# MainControl_A3.net
KiCad netlist of a schematic drawn in Altium Designer
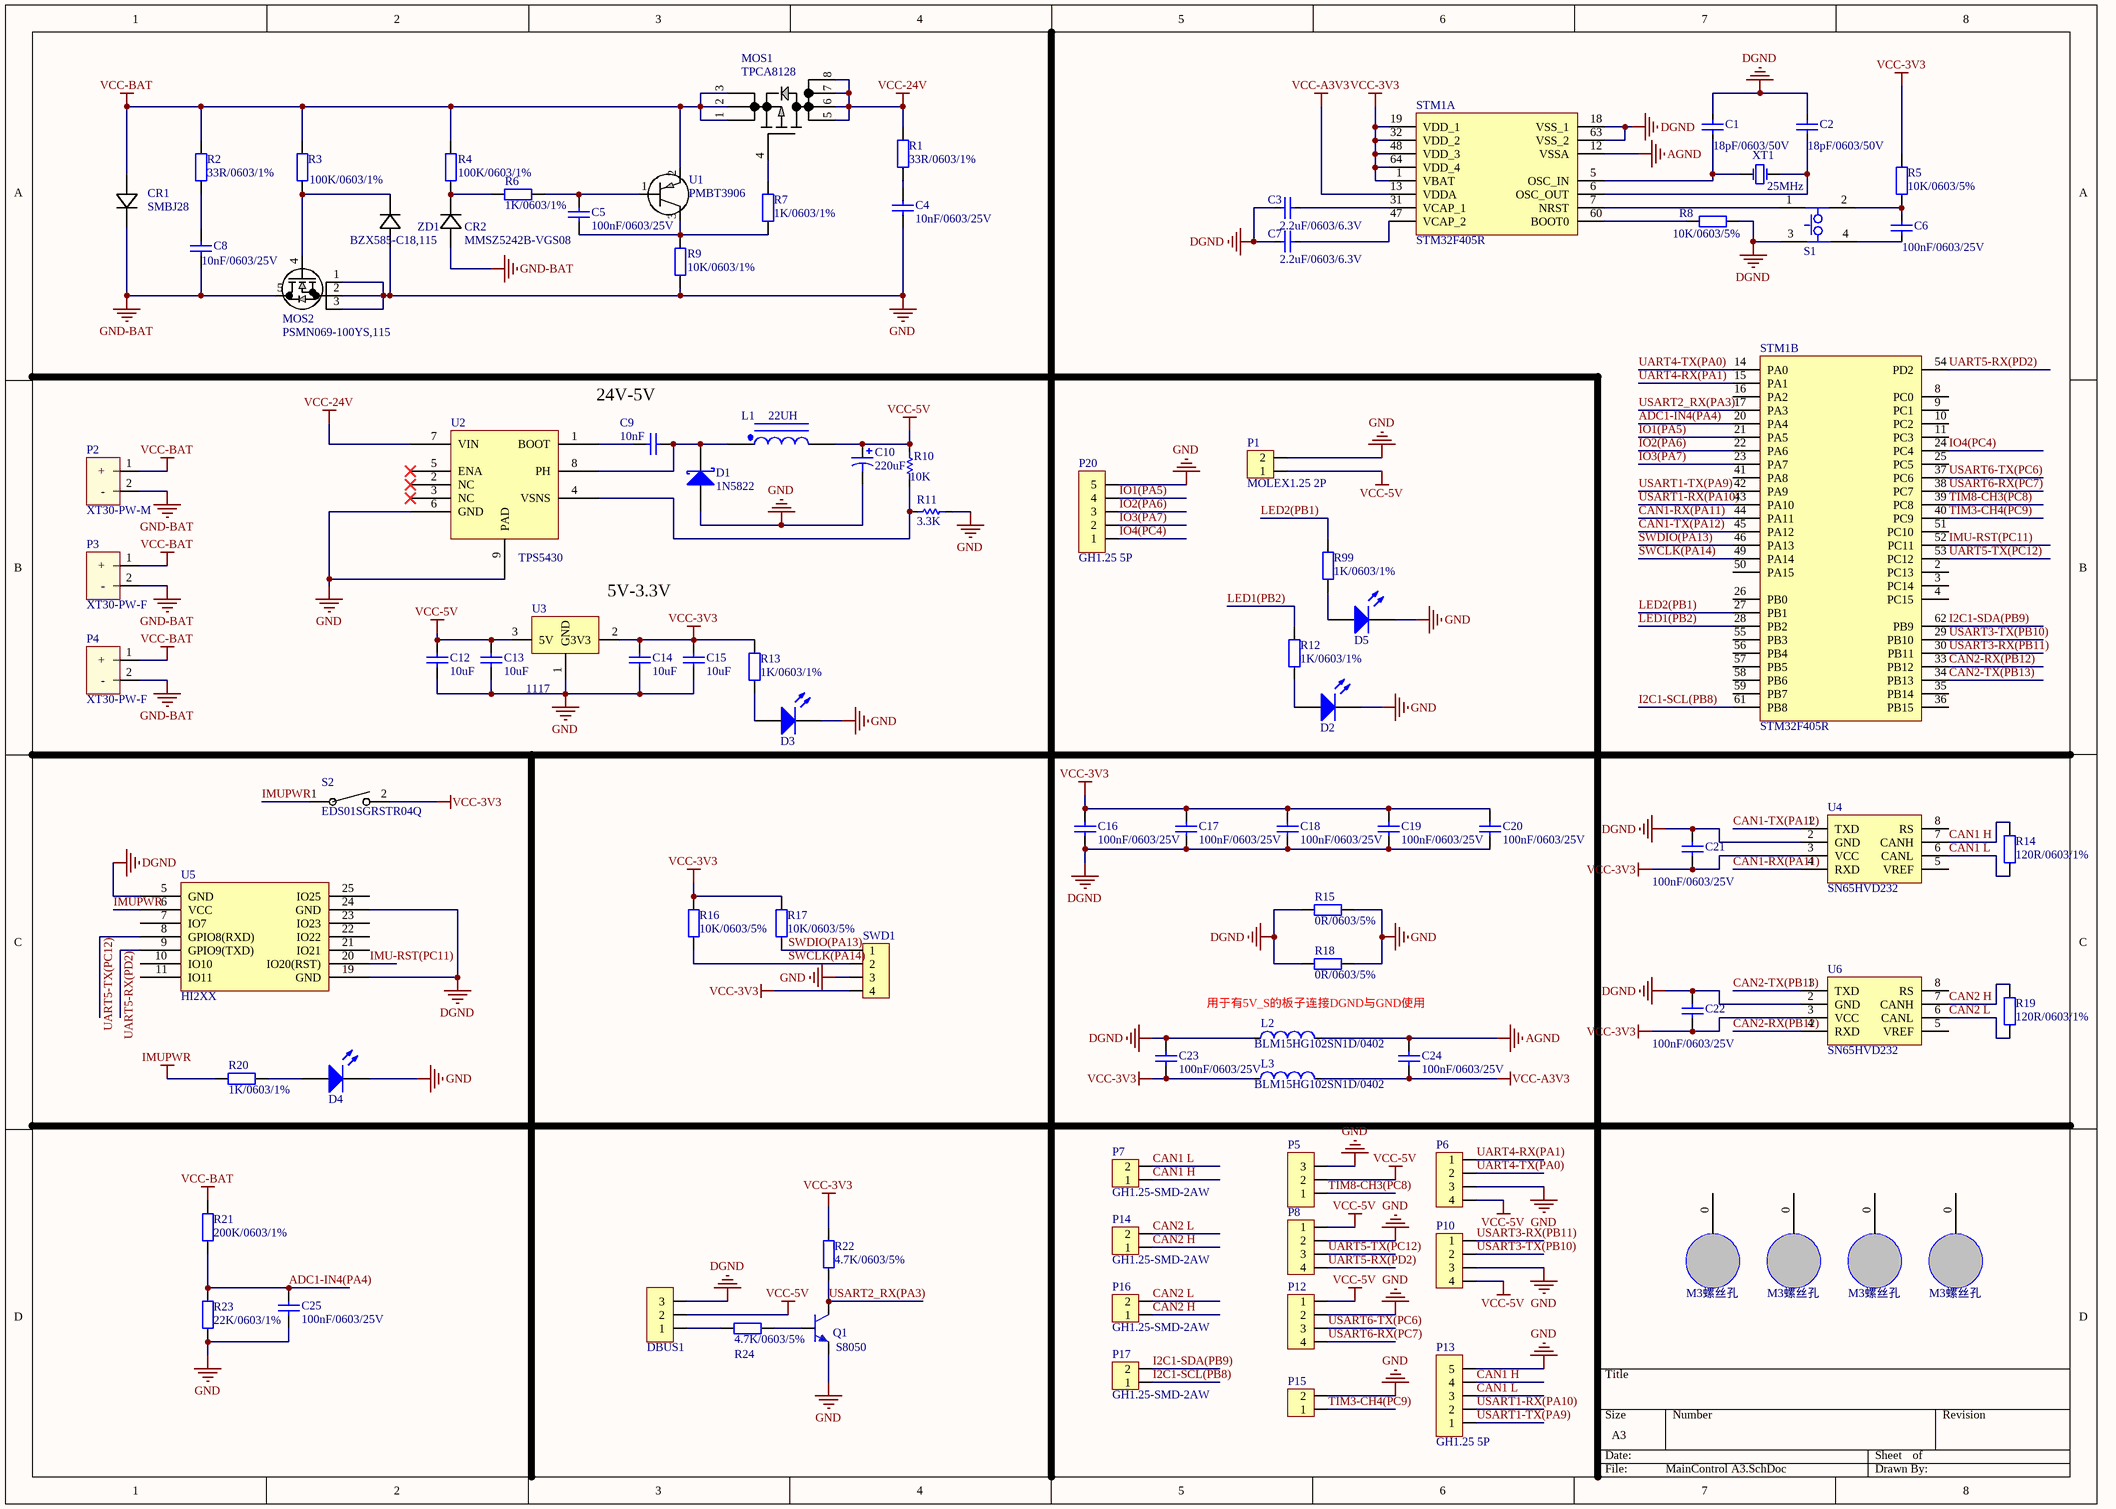
[diagram p0: MainControl A3.SchDoc]

(export (version "E")
  (design (tool "Eeschema 10.0.6"))
  (components
    (comp (ref "C1")
      (value "18pF/0603/50V")
      (footprint "C-SMD-0603")
      (description "Capacitor")
      (fields (field (name "Comment") "18pF"))
      (libsource (lib "SCH_Passive") (part "Cap_0402"))
    )
    (comp (ref "C2")
      (value "18pF/0603/50V")
      (footprint "C-SMD-0603")
      (description "Capacitor")
      (fields (field (name "Comment") "18pF"))
      (libsource (lib "SCH_Passive") (part "Cap_0402"))
    )
    (comp (ref "C3")
      (value "2.2uF/0603/6.3V")
      (footprint "C-SMD-0603")
      (description "Capacitor")
      (fields (field (name "Comment") "2.2uF"))
      (libsource (lib "SCH_Passive") (part "Cap_0402"))
    )
    (comp (ref "C4")
      (value "10nF/0603/25V")
      (footprint "C-SMD-0603")
      (description "贴片电容")
      (fields (field (name "Comment") "10nF") (field (name "PUBLISHER") "Altium Limited"))
      (libsource (lib "三代主控板原理图库") (part "Cap"))
    )
    (comp (ref "C5")
      (value "100nF/0603/25V")
      (footprint "C-SMD-0603")
      (description "贴片电容")
      (fields (field (name "Comment") "100nF") (field (name "PUBLISHER") "Altium Limited"))
      (libsource (lib "三代主控板原理图库") (part "Cap"))
    )
    (comp (ref "C6")
      (value "100nF/0603/25V")
      (footprint "C-SMD-0603")
      (description "Capacitor")
      (fields (field (name "Comment") "100nF"))
      (libsource (lib "SCH_Passive") (part "Cap_0402"))
    )
    (comp (ref "C7")
      (value "2.2uF/0603/6.3V")
      (footprint "C-SMD-0603")
      (description "Capacitor")
      (fields (field (name "Comment") "2.2uF"))
      (libsource (lib "SCH_Passive") (part "Cap_0402"))
    )
    (comp (ref "C8")
      (value "10nF/0603/25V")
      (footprint "C-SMD-0603")
      (description "贴片电容")
      (fields (field (name "Comment") "10nF") (field (name "PUBLISHER") "Altium Limited"))
      (libsource (lib "三代主控板原理图库") (part "Cap"))
    )
    (comp (ref "C9")
      (value "10nF")
      (footprint "C-SMD-0603")
      (description "无极性电容")
      (fields (field (name "PUBLISHER") "Altium Limited"))
      (libsource (lib "Devices") (part "Cap"))
    )
    (comp (ref "C10")
      (value "220uF")
      (footprint "TCAP7343")
      (description "Polarized Capacitor (Radial)")
      (fields (field (name "PUBLISHER") "Altium Limited"))
      (libsource (lib "Miscellaneous Devices") (part "Cap Pol1"))
    )
    (comp (ref "C12")
      (value "10uF")
      (footprint "C-SMD-0603")
      (description "无极性电容")
      (fields (field (name "PUBLISHER") "Altium Limited"))
      (libsource (lib "Devices") (part "Cap"))
    )
    (comp (ref "C13")
      (value "10uF")
      (footprint "C-SMD-0603")
      (description "无极性电容")
      (fields (field (name "PUBLISHER") "Altium Limited"))
      (libsource (lib "Devices") (part "Cap"))
    )
    (comp (ref "C14")
      (value "10uF")
      (footprint "C-SMD-0603")
      (description "无极性电容")
      (fields (field (name "PUBLISHER") "Altium Limited"))
      (libsource (lib "Devices") (part "Cap"))
    )
    (comp (ref "C15")
      (value "10uF")
      (footprint "C-SMD-0603")
      (description "无极性电容")
      (fields (field (name "PUBLISHER") "Altium Limited"))
      (libsource (lib "Devices") (part "Cap"))
    )
    (comp (ref "C16")
      (value "100nF/0603/25V")
      (footprint "C-SMD-0603")
      (description "贴片电容")
      (fields (field (name "Comment") "100nF") (field (name "PUBLISHER") "Altium Limited"))
      (libsource (lib "三代主控板原理图库") (part "Cap"))
    )
    (comp (ref "C17")
      (value "100nF/0603/25V")
      (footprint "C-SMD-0603")
      (description "贴片电容")
      (fields (field (name "Comment") "100nF") (field (name "PUBLISHER") "Altium Limited"))
      (libsource (lib "三代主控板原理图库") (part "Cap"))
    )
    (comp (ref "C18")
      (value "100nF/0603/25V")
      (footprint "C-SMD-0603")
      (description "贴片电容")
      (fields (field (name "Comment") "100nF") (field (name "PUBLISHER") "Altium Limited"))
      (libsource (lib "三代主控板原理图库") (part "Cap"))
    )
    (comp (ref "C19")
      (value "100nF/0603/25V")
      (footprint "C-SMD-0603")
      (description "贴片电容")
      (fields (field (name "Comment") "100nF") (field (name "PUBLISHER") "Altium Limited"))
      (libsource (lib "三代主控板原理图库") (part "Cap"))
    )
    (comp (ref "C20")
      (value "100nF/0603/25V")
      (footprint "C-SMD-0603")
      (description "贴片电容")
      (fields (field (name "Comment") "100nF") (field (name "PUBLISHER") "Altium Limited"))
      (libsource (lib "三代主控板原理图库") (part "Cap"))
    )
    (comp (ref "C21")
      (value "100nF/0603/25V")
      (footprint "C-SMD-0603")
      (description "贴片电容")
      (fields (field (name "Comment") "100NF") (field (name "PUBLISHER") "Altium Limited"))
      (libsource (lib "三代主控板原理图库") (part "Cap"))
    )
    (comp (ref "C22")
      (value "100nF/0603/25V")
      (footprint "C-SMD-0603")
      (description "贴片电容")
      (fields (field (name "Comment") "100NF") (field (name "PUBLISHER") "Altium Limited"))
      (libsource (lib "三代主控板原理图库") (part "Cap"))
    )
    (comp (ref "C23")
      (value "100nF/0603/25V")
      (footprint "C-SMD-0603")
      (description "贴片电容")
      (fields (field (name "Comment") "100nF") (field (name "PUBLISHER") "Altium Limited"))
      (libsource (lib "三代主控板原理图库") (part "Cap"))
    )
    (comp (ref "C24")
      (value "100nF/0603/25V")
      (footprint "C-SMD-0603")
      (description "贴片电容")
      (fields (field (name "Comment") "100nF") (field (name "PUBLISHER") "Altium Limited"))
      (libsource (lib "三代主控板原理图库") (part "Cap"))
    )
    (comp (ref "C25")
      (value "100nF/0603/25V")
      (footprint "C-SMD-0603")
      (description "贴片电容")
      (fields (field (name "Comment") "100nF") (field (name "PUBLISHER") "Altium Limited"))
      (libsource (lib "三代主控板原理图库") (part "Cap"))
    )
    (comp (ref "CR1")
      (value "SMBJ28")
      (footprint "SMBJSeries_LTF")
      (description "No Description Available")
      (fields
        (field (name "MANUFACTURER_PART_NUMBER") "SMBJ10")
        (field (name "COPYRIGHT") "Copyright (C) 2018 Accelerated Designs. All rights reserved")
      )
      (libsource (lib "SMBJ") (part "SMBJ10"))
    )
    (comp (ref "CR2")
      (value "MMSZ5242B-VGS08")
      (footprint "SOD123_MMS")
      (description "No Description Available")
      (fields (field (name "COPYRIGHT") "Copyright (C) 2018 Accelerated Designs. All rights reserved"))
      (libsource (lib "mmsz") (part "MMSZ5242B-VGS08"))
    )
    (comp (ref "D1")
      (value "1N5822")
      (footprint "SS34")
      (description "Schottky Diode")
      (fields (field (name "PUBLISHER") "Altium Limited"))
      (libsource (lib "Miscellaneous Devices") (part "D Schottky"))
    )
    (comp (ref "D2")
      (value "LED0")
      (footprint "LED-0603")
      (description "发光二极管")
      (fields (field (name "PUBLISHER") "Altium Limited"))
      (libsource (lib "Devices") (part "LED0"))
    )
    (comp (ref "D3")
      (value "LED0")
      (footprint "LED-0603")
      (description "发光二极管")
      (fields (field (name "PUBLISHER") "Altium Limited"))
      (libsource (lib "Devices") (part "LED0"))
    )
    (comp (ref "D4")
      (value "LED0")
      (footprint "LED-0603")
      (description "发光二极管")
      (fields (field (name "PUBLISHER") "Altium Limited"))
      (libsource (lib "Devices") (part "LED0"))
    )
    (comp (ref "D5")
      (value "LED0")
      (footprint "LED-0603")
      (description "发光二极管")
      (fields (field (name "PUBLISHER") "Altium Limited"))
      (libsource (lib "Devices") (part "LED0"))
    )
    (comp (ref "DBUS1")
      (value "Header 3")
      (footprint "HDR1x3")
      (description "Header")
      (fields (field (name "PUBLISHER") "Altium Limited"))
      (libsource (lib "排针排母") (part "Header 3"))
    )
    (comp (ref "L1")
      (value "22UH")
      (footprint "L-7070")
      (description "Magnetic-Core Inductor with Winding Polarity Marking")
      (fields (field (name "PUBLISHER") "Altium Limited"))
      (libsource (lib "Miscellaneous Devices") (part "Inductor Iron Dot"))
    )
    (comp (ref "L2")
      (value "BLM15HG102SN1D/0402")
      (footprint "l-SMD-0402")
      (description "Inductor")
      (fields (field (name "Comment") "BLM15HG102SN1D"))
      (libsource (lib "三代主控板原理图库") (part "BLM15HG102SN1D/0402"))
    )
    (comp (ref "L3")
      (value "BLM15HG102SN1D/0402")
      (footprint "l-SMD-0402")
      (description "Inductor")
      (fields (field (name "Comment") "BLM15HG102SN1D"))
      (libsource (lib "三代主控板原理图库") (part "BLM15HG102SN1D/0402"))
    )
    (comp (ref "M1") (value "M3螺丝孔") (footprint "M3螺丝") (libsource (lib "My_SCHLib") (part "M3螺丝孔")))
    (comp (ref "M2") (value "M3螺丝孔") (footprint "M3螺丝") (libsource (lib "My_SCHLib") (part "M3螺丝孔")))
    (comp (ref "M3") (value "M3螺丝孔") (footprint "M3螺丝") (libsource (lib "My_SCHLib") (part "M3螺丝孔")))
    (comp (ref "M4") (value "M3螺丝孔") (footprint "M3螺丝") (libsource (lib "My_SCHLib") (part "M3螺丝孔")))
    (comp (ref "MOS1")
      (value "TPCA8128")
      (footprint "SOP Advance_TOS")
      (description "No Description Available")
      (fields (field (name "COPYRIGHT") "Copyright (C) 2018 Accelerated Designs. All rights reserved"))
      (libsource (lib "TPCA8122") (part "TPCA8128"))
    )
    (comp (ref "MOS2")
      (value "PSMN069-100YS,115")
      (footprint "LFPAK56_POWER-SO8_SOT669_NEX")
      (description "No Description Available")
      (fields (field (name "COPYRIGHT") "Copyright (C) 2018 Accelerated Designs. All rights reserved"))
      (libsource (lib "psmn") (part "PSMN069-100YS,115"))
    )
    (comp (ref "P1")
      (value "MOLEX1.25 2P")
      (footprint "MOLEX1.25-2P")
      (description "pitch 1.25mm，2P，公座（A代表公，Y代表母），卧贴")
      (libsource (lib "SCH_Connector") (part "GH1.25-SMD-2AW"))
    )
    (comp (ref "P2")
      (value "XT30-PW-M")
      (footprint "XT30PW-M")
      (description "2P电源连接器母座")
      (libsource (lib "机器人队F405新主控1") (part "XT30-F"))
    )
    (comp (ref "P3")
      (value "XT30-PW-F")
      (footprint "XT30PW-F")
      (description "2P电源连接器母座")
      (libsource (lib "机器人队F405新主控1") (part "XT30-F"))
    )
    (comp (ref "P4")
      (value "XT30-PW-F")
      (footprint "XT30PW-F")
      (description "2P电源连接器母座")
      (libsource (lib "机器人队F405新主控1") (part "XT30-F"))
    )
    (comp (ref "P5")
      (value "Header 3")
      (footprint "HDR1X3")
      (description "Header")
      (fields (field (name "PUBLISHER") "Altium Limited"))
      (libsource (lib "排针排母") (part "Header 3"))
    )
    (comp (ref "P6")
      (value "GH1.25-SMD-4AW")
      (footprint "GH1.25-SMD-4AW")
      (description "pitch 1.25mm，4P，公座（A代表公，Y代表母），卧贴")
      (libsource (lib "") (part "GH1.25-SMD-4AW_1"))
    )
    (comp (ref "P7")
      (value "GH1.25-SMD-2AW")
      (footprint "GH1.25-SMD-2AW")
      (description "pitch 1.25mm，2P，公座（A代表公，Y代表母），卧贴")
      (libsource (lib "SCH_Connector") (part "GH1.25-SMD-2AW"))
    )
    (comp (ref "P8")
      (value "GH1.25-SMD-4AW")
      (footprint "GH1.25-SMD-4AW")
      (description "pitch 1.25mm，4P，公座（A代表公，Y代表母），卧贴")
      (libsource (lib "") (part "GH1.25-SMD-4AW_1"))
    )
    (comp (ref "P10")
      (value "GH1.25-SMD-4AW")
      (footprint "GH1.25-SMD-4AW")
      (description "pitch 1.25mm，4P，公座（A代表公，Y代表母），卧贴")
      (libsource (lib "") (part "GH1.25-SMD-4AW_1"))
    )
    (comp (ref "P12")
      (value "GH1.25-SMD-4AW")
      (footprint "GH1.25-SMD-4AW")
      (description "pitch 1.25mm，4P，公座（A代表公，Y代表母），卧贴")
      (libsource (lib "") (part "GH1.25-SMD-4AW_1"))
    )
    (comp (ref "P13")
      (value "GH1.25 5P")
      (footprint "GH1.25-SMD-5AW")
      (libsource (lib "gh1.25 5p") (part "GH1.25 5P"))
    )
    (comp (ref "P14")
      (value "GH1.25-SMD-2AW")
      (footprint "GH1.25-SMD-2AW")
      (description "pitch 1.25mm，2P，公座（A代表公，Y代表母），卧贴")
      (libsource (lib "SCH_Connector") (part "GH1.25-SMD-2AW"))
    )
    (comp (ref "P15")
      (value "GH1.25-SMD-2AW")
      (footprint "GH1.25-SMD-2AW")
      (description "pitch 1.25mm，2P，公座（A代表公，Y代表母），卧贴")
      (libsource (lib "SCH_Connector") (part "GH1.25-SMD-2AW"))
    )
    (comp (ref "P16")
      (value "GH1.25-SMD-2AW")
      (footprint "GH1.25-SMD-2AW")
      (description "pitch 1.25mm，2P，公座（A代表公，Y代表母），卧贴")
      (libsource (lib "SCH_Connector") (part "GH1.25-SMD-2AW"))
    )
    (comp (ref "P17")
      (value "GH1.25-SMD-2AW")
      (footprint "GH1.25-SMD-2AW")
      (description "pitch 1.25mm，2P，公座（A代表公，Y代表母），卧贴")
      (libsource (lib "SCH_Connector") (part "GH1.25-SMD-2AW"))
    )
    (comp (ref "P20")
      (value "GH1.25 5P")
      (footprint "GH1.25-SMD-5AW")
      (libsource (lib "gh1.25 5p") (part "GH1.25 5P"))
    )
    (comp (ref "Q1")
      (value "S8050")
      (footprint "SOT23-3")
      (description "Transistor")
      (libsource (lib "SCH_Active") (part "BJT_NPN"))
    )
    (comp (ref "R1")
      (value "33R/0603/1%")
      (footprint "R-SMD-0603")
      (description "贴片电阻")
      (fields (field (name "Comment") "33R") (field (name "PUBLISHER") "Altium Limited"))
      (libsource (lib "") (part "Res1_1"))
    )
    (comp (ref "R2")
      (value "33R/0603/1%")
      (footprint "R-SMD-0603")
      (description "贴片电阻")
      (fields (field (name "Comment") "33R") (field (name "PUBLISHER") "Altium Limited"))
      (libsource (lib "") (part "Res1_1"))
    )
    (comp (ref "R3")
      (value "100K/0603/1%")
      (footprint "R-SMD-0603")
      (description "贴片电阻")
      (fields (field (name "Comment") "100K") (field (name "PUBLISHER") "Altium Limited"))
      (libsource (lib "") (part "Res1_1"))
    )
    (comp (ref "R4")
      (value "100K/0603/1%")
      (footprint "R-SMD-0603")
      (description "贴片电阻")
      (fields (field (name "Comment") "100K") (field (name "PUBLISHER") "Altium Limited"))
      (libsource (lib "") (part "Res1_1"))
    )
    (comp (ref "R5")
      (value "10K/0603/5%")
      (footprint "R-SMD-0603")
      (description "Resistor")
      (fields (field (name "Comment") "10K"))
      (libsource (lib "") (part "Res_0402_2"))
    )
    (comp (ref "R6")
      (value "1K/0603/1%")
      (footprint "R-SMD-0603")
      (description "贴片电阻")
      (fields (field (name "Comment") "1K") (field (name "PUBLISHER") "Altium Limited"))
      (libsource (lib "") (part "Res1_2"))
    )
    (comp (ref "R7")
      (value "1K/0603/1%")
      (footprint "R-SMD-0603")
      (description "贴片电阻")
      (fields (field (name "Comment") "1K") (field (name "PUBLISHER") "Altium Limited"))
      (libsource (lib "底盘主控") (part "Res1"))
    )
    (comp (ref "R8")
      (value "10K/0603/5%")
      (footprint "R-SMD-0603")
      (description "Resistor")
      (fields (field (name "Comment") "10K"))
      (libsource (lib "SCH_Passive") (part "Res_0402"))
    )
    (comp (ref "R9")
      (value "10K/0603/1%")
      (footprint "R-SMD-0603")
      (description "贴片电阻")
      (fields (field (name "Comment") "10K") (field (name "PUBLISHER") "Altium Limited"))
      (libsource (lib "") (part "Res1_1"))
    )
    (comp (ref "R10")
      (value "10K")
      (footprint "R-SMD-0603")
      (description "贴片电阻")
      (fields (field (name "PUBLISHER") "Altium Limited"))
      (libsource (lib "Devices") (part "Res1"))
    )
    (comp (ref "R11")
      (value "3.3K")
      (footprint "R-SMD-0603")
      (description "贴片电阻")
      (fields (field (name "PUBLISHER") "Altium Limited"))
      (libsource (lib "Devices") (part "Res1"))
    )
    (comp (ref "R12")
      (value "1K/0603/1%")
      (footprint "R-SMD-0603")
      (description "贴片电阻")
      (fields (field (name "Comment") "1K") (field (name "PUBLISHER") "Altium Limited"))
      (libsource (lib "") (part "Res1_1"))
    )
    (comp (ref "R13")
      (value "1K/0603/1%")
      (footprint "R-SMD-0603")
      (description "贴片电阻")
      (fields (field (name "Comment") "1K") (field (name "PUBLISHER") "Altium Limited"))
      (libsource (lib "") (part "Res1_1"))
    )
    (comp (ref "R14")
      (value "120R/0603/1%")
      (footprint "R-SMD-0603")
      (description "贴片电阻")
      (fields (field (name "Comment") "120R"))
      (libsource (lib "三代主控板原理图库") (part "Res"))
    )
    (comp (ref "R15")
      (value "0R/0603/5%")
      (footprint "R-SMD-0603")
      (description "Resistor")
      (fields (field (name "Comment") "0R"))
      (libsource (lib "电容电阻电感") (part "Res_0603"))
    )
    (comp (ref "R16")
      (value "10K/0603/5%")
      (footprint "R-SMD-0603")
      (description "Resistor")
      (fields (field (name "Comment") "10K"))
      (libsource (lib "") (part "Res_0402_1"))
    )
    (comp (ref "R17")
      (value "10K/0603/5%")
      (footprint "R-SMD-0603")
      (description "Resistor")
      (fields (field (name "Comment") "10K"))
      (libsource (lib "") (part "Res_0402_1"))
    )
    (comp (ref "R18")
      (value "0R/0603/5%")
      (footprint "R-SMD-0603")
      (description "Resistor")
      (fields (field (name "Comment") "0R"))
      (libsource (lib "电容电阻电感") (part "Res_0603"))
    )
    (comp (ref "R19")
      (value "120R/0603/1%")
      (footprint "R-SMD-0603")
      (description "贴片电阻")
      (fields (field (name "Comment") "120R"))
      (libsource (lib "三代主控板原理图库") (part "Res"))
    )
    (comp (ref "R20")
      (value "1K/0603/1%")
      (footprint "R-SMD-0603")
      (description "贴片电阻")
      (fields (field (name "Comment") "1K") (field (name "PUBLISHER") "Altium Limited"))
      (libsource (lib "") (part "Res1_2"))
    )
    (comp (ref "R21")
      (value "200K/0603/1%")
      (footprint "R-SMD-0603")
      (description "贴片电阻")
      (fields (field (name "Comment") "200K") (field (name "PUBLISHER") "Altium Limited"))
      (libsource (lib "底盘主控") (part "Res1"))
    )
    (comp (ref "R22")
      (value "4.7K/0603/5%")
      (footprint "R-SMD-0603")
      (description "Resistor")
      (fields (field (name "Comment") "4.7K"))
      (libsource (lib "") (part "Res_0603_1"))
    )
    (comp (ref "R23")
      (value "22K/0603/1%")
      (footprint "R-SMD-0603")
      (description "贴片电阻")
      (fields (field (name "Comment") "22K") (field (name "PUBLISHER") "Altium Limited"))
      (libsource (lib "底盘主控") (part "Res1"))
    )
    (comp (ref "R24")
      (value "4.7K/0603/5%")
      (footprint "R-SMD-0603")
      (description "Resistor")
      (fields (field (name "Comment") "4.7K"))
      (libsource (lib "SCH_Passive") (part "Res_0603"))
    )
    (comp (ref "R99")
      (value "1K/0603/1%")
      (footprint "R-SMD-0603")
      (description "贴片电阻")
      (fields (field (name "Comment") "1K") (field (name "PUBLISHER") "Altium Limited"))
      (libsource (lib "") (part "Res1_1"))
    )
    (comp (ref "S1")
      (value "SKRPADE010")
      (footprint "SKRPADE010")
      (description "Switch")
      (fields (field (name "PUBLISHER") "Altium Limited"))
      (libsource (lib "SCH_Switch") (part "SKRPADE010"))
    )
    (comp (ref "S2")
      (value "EDS01SGRSTR04Q")
      (footprint "SW1_EDS01SGRSTR04Q_TEC-M")
      (description "No Description Available")
      (fields (field (name "COPYRIGHT") "Copyright (C) 2018 Accelerated Designs. All rights reserved"))
      (libsource (lib "switch1") (part "EDS01SGRSTR04Q"))
    )
    (comp (ref "STM1")
      (value "STM32F405R")
      (footprint "LQFP64")
      (description "MCU")
      (libsource (lib "SCH_IC") (part "STM32F405R"))
    )
    (comp (ref "SWD1")
      (value "GH1.25-SMD-4AW")
      (footprint "molex1.25-4p")
      (description "pitch 1.25mm，4P，公座（A代表公，Y代表母），卧贴")
      (libsource (lib "SCH_Connector") (part "GH1.25-SMD-4AW"))
    )
    (comp (ref "U1")
      (value "PMBT3906")
      (footprint "SOT23_NEX")
      (description "No Description Available")
      (fields (field (name "COPYRIGHT") "Copyright (C) 2016 Accelerated Designs. All rights reserved"))
      (libsource (lib "PBMT3906") (part "PMBT3906"))
    )
    (comp (ref "U2") (value "TPS5430") (footprint "TPS5430") (libsource (lib "Schlib1") (part "TPS5430")))
    (comp (ref "U3") (value "1117") (footprint "AMS1117") (libsource (lib "SHAWN") (part "AMS1117-3.3")))
    (comp (ref "U4")
      (value "SN65HVD232")
      (footprint "SOP-8")
      (description "CAN")
      (libsource (lib "SCH_IC") (part "SN65HVD232"))
    )
    (comp (ref "U5")
      (value "HI2XX")
      (footprint "HI2XX_PLCC28")
      (libsource (lib "HI226_HI229") (part "HI2XX"))
    )
    (comp (ref "U6")
      (value "SN65HVD232")
      (footprint "SOP-8")
      (description "CAN")
      (libsource (lib "SCH_IC") (part "SN65HVD232"))
    )
    (comp (ref "XT1")
      (value "25MHz")
      (footprint "XTAL3225")
      (description "Crystal Oscillator")
      (fields (field (name "PUBLISHER") "Altium Limited"))
      (libsource (lib "SCH_Oscillator") (part "XTAL_5032"))
    )
    (comp (ref "ZD1")
      (value "BZX585-C18,115")
      (footprint "CR_85-C18,115_NEX")
      (description "No Description Available")
      (fields (field (name "COPYRIGHT") "Copyright (C) 2018 Accelerated Designs. All rights reserved"))
      (libsource (lib "bzx58") (part "BZX585-C18,115"))
    )
  )
  (nets
    (net (code "1") (name "/ADC1-IN4(PA4)") (class "Default")
      (node (ref "C25") (pin "2") (pinfunction "2_2") (pintype "passive"))
      (node (ref "R21") (pin "1") (pinfunction "1_1") (pintype "passive"))
      (node (ref "R23") (pin "2") (pinfunction "2_2") (pintype "passive"))
      (node (ref "STM1") (pin "20") (pinfunction "PA4_20") (pintype "passive"))
    )
    (net (code "2") (name "/CAN1 H") (class "Default")
      (node (ref "P13") (pin "4") (pinfunction "4_4") (pintype "passive"))
      (node (ref "P7") (pin "1") (pinfunction "1_1") (pintype "passive"))
      (node (ref "R14") (pin "2") (pinfunction "2_2") (pintype "passive"))
      (node (ref "U4") (pin "7") (pinfunction "CANH_7") (pintype "passive"))
    )
    (net (code "3") (name "/CAN1 L") (class "Default")
      (node (ref "P13") (pin "3") (pinfunction "3_3") (pintype "passive"))
      (node (ref "P7") (pin "2") (pinfunction "2_2") (pintype "passive"))
      (node (ref "R14") (pin "1") (pinfunction "1_1") (pintype "passive"))
      (node (ref "U4") (pin "6") (pinfunction "CANL_6") (pintype "passive"))
    )
    (net (code "4") (name "/CAN1-RX(PA11)") (class "Default")
      (node (ref "STM1") (pin "44") (pinfunction "PA11_44") (pintype "passive"))
      (node (ref "U4") (pin "4") (pinfunction "RXD_4") (pintype "passive"))
    )
    (net (code "5") (name "/CAN1-TX(PA12)") (class "Default")
      (node (ref "STM1") (pin "45") (pinfunction "PA12_45") (pintype "passive"))
      (node (ref "U4") (pin "1") (pinfunction "TXD_1") (pintype "passive"))
    )
    (net (code "6") (name "/CAN2 H") (class "Default")
      (node (ref "P14") (pin "1") (pinfunction "1_1") (pintype "passive"))
      (node (ref "P16") (pin "1") (pinfunction "1_1") (pintype "passive"))
      (node (ref "R19") (pin "2") (pinfunction "2_2") (pintype "passive"))
      (node (ref "U6") (pin "7") (pinfunction "CANH_7") (pintype "passive"))
    )
    (net (code "7") (name "/CAN2 L") (class "Default")
      (node (ref "P14") (pin "2") (pinfunction "2_2") (pintype "passive"))
      (node (ref "P16") (pin "2") (pinfunction "2_2") (pintype "passive"))
      (node (ref "R19") (pin "1") (pinfunction "1_1") (pintype "passive"))
      (node (ref "U6") (pin "6") (pinfunction "CANL_6") (pintype "passive"))
    )
    (net (code "8") (name "/CAN2-RX(PB12)") (class "Default")
      (node (ref "STM1") (pin "33") (pinfunction "PB12_33") (pintype "passive"))
      (node (ref "U6") (pin "4") (pinfunction "RXD_4") (pintype "passive"))
    )
    (net (code "9") (name "/CAN2-TX(PB13)") (class "Default")
      (node (ref "STM1") (pin "34") (pinfunction "PB13_34") (pintype "passive"))
      (node (ref "U6") (pin "1") (pinfunction "TXD_1") (pintype "passive"))
    )
    (net (code "10") (name "/I2C1-SCL(PB8)") (class "Default")
      (node (ref "P17") (pin "1") (pinfunction "1_1") (pintype "passive"))
      (node (ref "STM1") (pin "61") (pinfunction "PB8_61") (pintype "passive"))
    )
    (net (code "11") (name "/I2C1-SDA(PB9)") (class "Default")
      (node (ref "P17") (pin "2") (pinfunction "2_2") (pintype "passive"))
      (node (ref "STM1") (pin "62") (pinfunction "PB9_62") (pintype "passive"))
    )
    (net (code "12") (name "/IMU-RST(PC11)") (class "Default")
      (node (ref "STM1") (pin "52") (pinfunction "PC11_52") (pintype "passive"))
      (node (ref "U5") (pin "20") (pinfunction "IO20(RST)_20") (pintype "passive"))
    )
    (net (code "13") (name "/IO1(PA5)") (class "Default")
      (node (ref "P20") (pin "4") (pinfunction "4_4") (pintype "passive"))
      (node (ref "STM1") (pin "21") (pinfunction "PA5_21") (pintype "passive"))
    )
    (net (code "14") (name "/IO2(PA6)") (class "Default")
      (node (ref "P20") (pin "3") (pinfunction "3_3") (pintype "passive"))
      (node (ref "STM1") (pin "22") (pinfunction "PA6_22") (pintype "passive"))
    )
    (net (code "15") (name "/IO3(PA7)") (class "Default")
      (node (ref "P20") (pin "2") (pinfunction "2_2") (pintype "passive"))
      (node (ref "STM1") (pin "23") (pinfunction "PA7_23") (pintype "passive"))
    )
    (net (code "16") (name "/IO4(PC4)") (class "Default")
      (node (ref "P20") (pin "1") (pinfunction "1_1") (pintype "passive"))
      (node (ref "STM1") (pin "24") (pinfunction "PC4_24") (pintype "passive"))
    )
    (net (code "17") (name "/LED1(PB2)") (class "Default")
      (node (ref "R12") (pin "1") (pinfunction "1_1") (pintype "passive"))
      (node (ref "STM1") (pin "28") (pinfunction "PB2_28") (pintype "passive"))
    )
    (net (code "18") (name "/LED2(PB1)") (class "Default")
      (node (ref "R99") (pin "1") (pinfunction "1_1") (pintype "passive"))
      (node (ref "STM1") (pin "27") (pinfunction "PB1_27") (pintype "passive"))
    )
    (net (code "19") (name "/SWCLK(PA14)") (class "Default")
      (node (ref "R16") (pin "2") (pinfunction "2_2") (pintype "passive"))
      (node (ref "STM1") (pin "49") (pinfunction "PA14_49") (pintype "passive"))
      (node (ref "SWD1") (pin "2") (pinfunction "2_2") (pintype "passive"))
    )
    (net (code "20") (name "/SWDIO(PA13)") (class "Default")
      (node (ref "R17") (pin "2") (pinfunction "2_2") (pintype "passive"))
      (node (ref "STM1") (pin "46") (pinfunction "PA13_46") (pintype "passive"))
      (node (ref "SWD1") (pin "1") (pinfunction "1_1") (pintype "passive"))
    )
    (net (code "21") (name "/TIM3-CH4(PC9)") (class "Default")
      (node (ref "P15") (pin "1") (pinfunction "1_1") (pintype "passive"))
      (node (ref "STM1") (pin "40") (pinfunction "PC9_40") (pintype "passive"))
    )
    (net (code "22") (name "/TIM8-CH3(PC8)") (class "Default")
      (node (ref "P5") (pin "1") (pinfunction "1_1") (pintype "passive"))
      (node (ref "STM1") (pin "39") (pinfunction "PC8_39") (pintype "passive"))
    )
    (net (code "23") (name "/UART4-RX(PA1)") (class "Default")
      (node (ref "P6") (pin "1") (pinfunction "1_1") (pintype "passive"))
      (node (ref "STM1") (pin "15") (pinfunction "PA1_15") (pintype "passive"))
    )
    (net (code "24") (name "/UART4-TX(PA0)") (class "Default")
      (node (ref "P6") (pin "2") (pinfunction "2_2") (pintype "passive"))
      (node (ref "STM1") (pin "14") (pinfunction "PA0_14") (pintype "passive"))
    )
    (net (code "25") (name "/UART5-RX(PD2)") (class "Default")
      (node (ref "P8") (pin "4") (pinfunction "4_4") (pintype "passive"))
      (node (ref "STM1") (pin "54") (pinfunction "PD2_54") (pintype "passive"))
      (node (ref "U5") (pin "9") (pinfunction "GPIO9(TXD)_9") (pintype "passive"))
    )
    (net (code "26") (name "/UART5-TX(PC12)") (class "Default")
      (node (ref "P8") (pin "3") (pinfunction "3_3") (pintype "passive"))
      (node (ref "STM1") (pin "53") (pinfunction "PC12_53") (pintype "passive"))
      (node (ref "U5") (pin "8") (pinfunction "GPIO8(RXD)_8") (pintype "passive"))
    )
    (net (code "27") (name "/USART1-RX(PA10)") (class "Default")
      (node (ref "P13") (pin "2") (pinfunction "2_2") (pintype "passive"))
      (node (ref "STM1") (pin "43") (pinfunction "PA10_43") (pintype "passive"))
    )
    (net (code "28") (name "/USART1-TX(PA9)") (class "Default")
      (node (ref "P13") (pin "1") (pinfunction "1_1") (pintype "passive"))
      (node (ref "STM1") (pin "42") (pinfunction "PA9_42") (pintype "passive"))
    )
    (net (code "29") (name "/USART2_RX(PA3)") (class "Default")
      (node (ref "Q1") (pin "3") (pinfunction "C_3") (pintype "passive"))
      (node (ref "R22") (pin "2") (pinfunction "2_2") (pintype "passive"))
      (node (ref "STM1") (pin "17") (pinfunction "PA3_17") (pintype "passive"))
    )
    (net (code "30") (name "/USART3-RX(PB11)") (class "Default")
      (node (ref "P10") (pin "1") (pinfunction "1_1") (pintype "passive"))
      (node (ref "STM1") (pin "30") (pinfunction "PB11_30") (pintype "passive"))
    )
    (net (code "31") (name "/USART3-TX(PB10)") (class "Default")
      (node (ref "P10") (pin "2") (pinfunction "2_2") (pintype "passive"))
      (node (ref "STM1") (pin "29") (pinfunction "PB10_29") (pintype "passive"))
    )
    (net (code "32") (name "/USART6-RX(PC7)") (class "Default")
      (node (ref "P12") (pin "4") (pinfunction "4_4") (pintype "passive"))
      (node (ref "STM1") (pin "38") (pinfunction "PC7_38") (pintype "passive"))
    )
    (net (code "33") (name "/USART6-TX(PC6)") (class "Default")
      (node (ref "P12") (pin "3") (pinfunction "3_3") (pintype "passive"))
      (node (ref "STM1") (pin "37") (pinfunction "PC6_37") (pintype "passive"))
    )
    (net (code "34") (name "AGND") (class "Default")
      (node (ref "C24") (pin "2") (pinfunction "2_2") (pintype "passive"))
      (node (ref "L2") (pin "2") (pinfunction "2_2") (pintype "passive"))
      (node (ref "STM1") (pin "12") (pinfunction "VSSA_12") (pintype "passive"))
    )
    (net (code "35") (name "DGND") (class "Default")
      (node (ref "C1") (pin "2") (pinfunction "2_2") (pintype "passive"))
      (node (ref "C16") (pin "1") (pinfunction "1_1") (pintype "passive"))
      (node (ref "C17") (pin "1") (pinfunction "1_1") (pintype "passive"))
      (node (ref "C18") (pin "1") (pinfunction "1_1") (pintype "passive"))
      (node (ref "C19") (pin "1") (pinfunction "1_1") (pintype "passive"))
      (node (ref "C2") (pin "2") (pinfunction "2_2") (pintype "passive"))
      (node (ref "C20") (pin "1") (pinfunction "1_1") (pintype "passive"))
      (node (ref "C21") (pin "2") (pinfunction "2_2") (pintype "passive"))
      (node (ref "C22") (pin "2") (pinfunction "2_2") (pintype "passive"))
      (node (ref "C23") (pin "2") (pinfunction "2_2") (pintype "passive"))
      (node (ref "C3") (pin "2") (pinfunction "2_2") (pintype "passive"))
      (node (ref "C7") (pin "2") (pinfunction "2_2") (pintype "passive"))
      (node (ref "DBUS1") (pin "3") (pinfunction "3_3") (pintype "passive"))
      (node (ref "L2") (pin "1") (pinfunction "1_1") (pintype "passive"))
      (node (ref "R15") (pin "1") (pinfunction "1_1") (pintype "passive"))
      (node (ref "R18") (pin "1") (pinfunction "1_1") (pintype "passive"))
      (node (ref "R8") (pin "1") (pinfunction "1_1") (pintype "passive"))
      (node (ref "S1") (pin "3") (pinfunction "B1_3") (pintype "passive"))
      (node (ref "STM1") (pin "18") (pinfunction "VSS_1_18") (pintype "passive"))
      (node (ref "STM1") (pin "63") (pinfunction "VSS_2_63") (pintype "passive"))
      (node (ref "U4") (pin "2") (pinfunction "GND_2") (pintype "passive"))
      (node (ref "U5") (pin "19") (pinfunction "GND_19") (pintype "passive"))
      (node (ref "U5") (pin "24") (pinfunction "GND_24") (pintype "passive"))
      (node (ref "U5") (pin "5") (pinfunction "GND_5") (pintype "passive"))
      (node (ref "U6") (pin "2") (pinfunction "GND_2") (pintype "passive"))
    )
    (net (code "36") (name "GND") (class "Default")
      (node (ref "C10") (pin "2") (pinfunction "2_2") (pintype "passive"))
      (node (ref "C12") (pin "1") (pinfunction "1_1") (pintype "passive"))
      (node (ref "C13") (pin "1") (pinfunction "1_1") (pintype "passive"))
      (node (ref "C14") (pin "1") (pinfunction "1_1") (pintype "passive"))
      (node (ref "C15") (pin "1") (pinfunction "1_1") (pintype "passive"))
      (node (ref "C25") (pin "1") (pinfunction "1_1") (pintype "passive"))
      (node (ref "C4") (pin "1") (pinfunction "1_1") (pintype "passive"))
      (node (ref "D1") (pin "1") (pinfunction "A_1") (pintype "passive"))
      (node (ref "D2") (pin "2") (pinfunction "K_2") (pintype "passive"))
      (node (ref "D3") (pin "2") (pinfunction "K_2") (pintype "passive"))
      (node (ref "D4") (pin "2") (pinfunction "K_2") (pintype "passive"))
      (node (ref "D5") (pin "2") (pinfunction "K_2") (pintype "passive"))
      (node (ref "MOS2") (pin "1") (pinfunction "S_1") (pintype "passive"))
      (node (ref "MOS2") (pin "2") (pinfunction "S_2") (pintype "passive"))
      (node (ref "MOS2") (pin "3") (pinfunction "S_3") (pintype "passive"))
      (node (ref "P1") (pin "2") (pinfunction "2_2") (pintype "passive"))
      (node (ref "P10") (pin "3") (pinfunction "3_3") (pintype "passive"))
      (node (ref "P12") (pin "2") (pinfunction "2_2") (pintype "passive"))
      (node (ref "P13") (pin "5") (pinfunction "5_5") (pintype "passive"))
      (node (ref "P15") (pin "2") (pinfunction "2_2") (pintype "passive"))
      (node (ref "P20") (pin "5") (pinfunction "5_5") (pintype "passive"))
      (node (ref "P5") (pin "3") (pinfunction "3_3") (pintype "passive"))
      (node (ref "P6") (pin "3") (pinfunction "3_3") (pintype "passive"))
      (node (ref "P8") (pin "2") (pinfunction "2_2") (pintype "passive"))
      (node (ref "Q1") (pin "2") (pinfunction "E_2") (pintype "passive"))
      (node (ref "R11") (pin "1") (pinfunction "TOP_1") (pintype "passive"))
      (node (ref "R15") (pin "2") (pinfunction "2_2") (pintype "passive"))
      (node (ref "R18") (pin "2") (pinfunction "2_2") (pintype "passive"))
      (node (ref "R23") (pin "1") (pinfunction "1_1") (pintype "passive"))
      (node (ref "R9") (pin "2") (pinfunction "2_2") (pintype "passive"))
      (node (ref "SWD1") (pin "3") (pinfunction "3_3") (pintype "passive"))
      (node (ref "U2") (pin "6") (pinfunction "GND_6") (pintype "power_in"))
      (node (ref "U2") (pin "9") (pinfunction "PAD_9") (pintype "power_in"))
      (node (ref "U3") (pin "1") (pinfunction "GND_1") (pintype "passive"))
      (node (ref "ZD1") (pin "2") (pinfunction "2_2") (pintype "passive"))
    )
    (net (code "37") (name "GND-BAT") (class "Default")
      (node (ref "C8") (pin "1") (pinfunction "1_1") (pintype "passive"))
      (node (ref "CR1") (pin "1") (pinfunction "11_1") (pintype "passive"))
      (node (ref "CR2") (pin "2") (pinfunction "2_2") (pintype "passive"))
      (node (ref "MOS2") (pin "5") (pinfunction "D_5") (pintype "passive"))
      (node (ref "P2") (pin "2") (pinfunction "-_2") (pintype "passive"))
      (node (ref "P3") (pin "2") (pinfunction "-_2") (pintype "passive"))
      (node (ref "P4") (pin "2") (pinfunction "-_2") (pintype "passive"))
    )
    (net (code "38") (name "IMUPWR") (class "Default")
      (node (ref "R20") (pin "1") (pinfunction "1_1") (pintype "passive"))
      (node (ref "S2") (pin "1") (pinfunction "1_1") (pintype "passive"))
      (node (ref "U5") (pin "6") (pinfunction "VCC_6") (pintype "passive"))
    )
    (net (code "39") (name "Net-(C4-Pad2)") (class "Default")
      (node (ref "C4") (pin "2") (pinfunction "2_2") (pintype "passive"))
      (node (ref "R1") (pin "2") (pinfunction "2_2") (pintype "passive"))
    )
    (net (code "40") (name "Net-(C5-Pad1)") (class "Default")
      (node (ref "C5") (pin "1") (pinfunction "1_1") (pintype "passive"))
      (node (ref "R7") (pin "1") (pinfunction "1_1") (pintype "passive"))
      (node (ref "R9") (pin "1") (pinfunction "1_1") (pintype "passive"))
      (node (ref "U1") (pin "3") (pinfunction "3_3") (pintype "passive"))
    )
    (net (code "41") (name "Net-(C5-Pad2)") (class "Default")
      (node (ref "C5") (pin "2") (pinfunction "2_2") (pintype "passive"))
      (node (ref "R6") (pin "2") (pinfunction "2_2") (pintype "passive"))
      (node (ref "U1") (pin "1") (pinfunction "1_1") (pintype "passive"))
    )
    (net (code "42") (name "Net-(C8-Pad2)") (class "Default")
      (node (ref "C8") (pin "2") (pinfunction "2_2") (pintype "passive"))
      (node (ref "R2") (pin "2") (pinfunction "2_2") (pintype "passive"))
    )
    (net (code "43") (name "Net-(CR2-Pad1)") (class "Default")
      (node (ref "CR2") (pin "1") (pinfunction "1_1") (pintype "passive"))
      (node (ref "R4") (pin "2") (pinfunction "2_2") (pintype "passive"))
      (node (ref "R6") (pin "1") (pinfunction "1_1") (pintype "passive"))
    )
    (net (code "44") (name "Net-(D1-K)") (class "Default")
      (node (ref "C9") (pin "2") (pinfunction "2_2") (pintype "passive"))
      (node (ref "D1") (pin "2") (pinfunction "K_2") (pintype "passive"))
      (node (ref "L1") (pin "1") (pinfunction "1_1") (pintype "passive"))
      (node (ref "U2") (pin "8") (pinfunction "PH_8") (pintype "power_in"))
    )
    (net (code "45") (name "Net-(D2-A)") (class "Default")
      (node (ref "D2") (pin "1") (pinfunction "A_1") (pintype "passive"))
      (node (ref "R12") (pin "2") (pinfunction "2_2") (pintype "passive"))
    )
    (net (code "46") (name "Net-(D3-A)") (class "Default")
      (node (ref "D3") (pin "1") (pinfunction "A_1") (pintype "passive"))
      (node (ref "R13") (pin "2") (pinfunction "2_2") (pintype "passive"))
    )
    (net (code "47") (name "Net-(D4-A)") (class "Default")
      (node (ref "D4") (pin "1") (pinfunction "A_1") (pintype "passive"))
      (node (ref "R20") (pin "2") (pinfunction "2_2") (pintype "passive"))
    )
    (net (code "48") (name "Net-(D5-A)") (class "Default")
      (node (ref "D5") (pin "1") (pinfunction "A_1") (pintype "passive"))
      (node (ref "R99") (pin "2") (pinfunction "2_2") (pintype "passive"))
    )
    (net (code "49") (name "Net-(DBUS1-Pad1)") (class "Default")
      (node (ref "DBUS1") (pin "1") (pinfunction "1_1") (pintype "passive"))
      (node (ref "R24") (pin "2") (pinfunction "2_2") (pintype "passive"))
    )
    (net (code "50") (name "Net-(MOS1-2)") (class "Default")
      (node (ref "MOS1") (pin "4") (pinfunction "2_4") (pintype "passive"))
      (node (ref "R7") (pin "2") (pinfunction "2_2") (pintype "passive"))
    )
    (net (code "51") (name "Net-(MOS2-G)") (class "Default")
      (node (ref "MOS2") (pin "4") (pinfunction "G_4") (pintype "passive"))
      (node (ref "R3") (pin "2") (pinfunction "2_2") (pintype "passive"))
      (node (ref "ZD1") (pin "1") (pinfunction "1_1") (pintype "passive"))
    )
    (net (code "52") (name "Net-(Q1-B)") (class "Default")
      (node (ref "Q1") (pin "1") (pinfunction "B_1") (pintype "passive"))
      (node (ref "R24") (pin "1") (pinfunction "1_1") (pintype "passive"))
    )
    (net (code "53") (name "Net-(R10-BOT)") (class "Default")
      (node (ref "R10") (pin "2") (pinfunction "BOT_2") (pintype "passive"))
      (node (ref "R11") (pin "2") (pinfunction "BOT_2") (pintype "passive"))
      (node (ref "U2") (pin "4") (pinfunction "VSNS_4") (pintype "power_in"))
    )
    (net (code "54") (name "Net-(S1-A1)") (class "Default")
      (node (ref "S1") (pin "1") (pinfunction "A1_1") (pintype "passive"))
      (node (ref "STM1") (pin "7") (pinfunction "NRST_7") (pintype "passive"))
    )
    (net (code "55") (name "Net-(S1-A2)") (class "Default")
      (node (ref "C6") (pin "2") (pinfunction "2_2") (pintype "passive"))
      (node (ref "R5") (pin "1") (pinfunction "1_1") (pintype "passive"))
      (node (ref "S1") (pin "2") (pinfunction "A2_2") (pintype "passive"))
    )
    (net (code "56") (name "Net-(S1-B2)") (class "Default")
      (node (ref "C6") (pin "1") (pinfunction "1_1") (pintype "passive"))
      (node (ref "S1") (pin "4") (pinfunction "B2_4") (pintype "passive"))
    )
    (net (code "57") (name "Net-(STM1A-BOOT0)") (class "Default")
      (node (ref "R8") (pin "2") (pinfunction "2_2") (pintype "passive"))
      (node (ref "STM1") (pin "60") (pinfunction "BOOT0_60") (pintype "passive"))
    )
    (net (code "58") (name "Net-(STM1A-OSC_IN)") (class "Default")
      (node (ref "C1") (pin "1") (pinfunction "1_1") (pintype "passive"))
      (node (ref "STM1") (pin "5") (pinfunction "OSC_IN_5") (pintype "passive"))
      (node (ref "XT1") (pin "1") (pinfunction "OSC1_1") (pintype "passive"))
    )
    (net (code "59") (name "Net-(STM1A-OSC_OUT)") (class "Default")
      (node (ref "C2") (pin "1") (pinfunction "1_1") (pintype "passive"))
      (node (ref "STM1") (pin "6") (pinfunction "OSC_OUT_6") (pintype "passive"))
      (node (ref "XT1") (pin "3") (pinfunction "OSC2_3") (pintype "passive"))
    )
    (net (code "60") (name "Net-(STM1A-VCAP_1)") (class "Default")
      (node (ref "C3") (pin "1") (pinfunction "1_1") (pintype "passive"))
      (node (ref "STM1") (pin "31") (pinfunction "VCAP_1_31") (pintype "passive"))
    )
    (net (code "61") (name "Net-(STM1A-VCAP_2)") (class "Default")
      (node (ref "C7") (pin "1") (pinfunction "1_1") (pintype "passive"))
      (node (ref "STM1") (pin "47") (pinfunction "VCAP_2_47") (pintype "passive"))
    )
    (net (code "62") (name "Net-(U2-BOOT)") (class "Default")
      (node (ref "C9") (pin "1") (pinfunction "1_1") (pintype "passive"))
      (node (ref "U2") (pin "1") (pinfunction "BOOT_1") (pintype "power_in"))
    )
    (net (code "63") (name "VCC-3V3") (class "Default")
      (node (ref "C14") (pin "2") (pinfunction "2_2") (pintype "passive"))
      (node (ref "C15") (pin "2") (pinfunction "2_2") (pintype "passive"))
      (node (ref "C16") (pin "2") (pinfunction "2_2") (pintype "passive"))
      (node (ref "C17") (pin "2") (pinfunction "2_2") (pintype "passive"))
      (node (ref "C18") (pin "2") (pinfunction "2_2") (pintype "passive"))
      (node (ref "C19") (pin "2") (pinfunction "2_2") (pintype "passive"))
      (node (ref "C20") (pin "2") (pinfunction "2_2") (pintype "passive"))
      (node (ref "C21") (pin "1") (pinfunction "1_1") (pintype "passive"))
      (node (ref "C22") (pin "1") (pinfunction "1_1") (pintype "passive"))
      (node (ref "C23") (pin "1") (pinfunction "1_1") (pintype "passive"))
      (node (ref "L3") (pin "1") (pinfunction "1_1") (pintype "passive"))
      (node (ref "R13") (pin "1") (pinfunction "1_1") (pintype "passive"))
      (node (ref "R16") (pin "1") (pinfunction "1_1") (pintype "passive"))
      (node (ref "R17") (pin "1") (pinfunction "1_1") (pintype "passive"))
      (node (ref "R22") (pin "1") (pinfunction "1_1") (pintype "passive"))
      (node (ref "R5") (pin "2") (pinfunction "2_2") (pintype "passive"))
      (node (ref "S2") (pin "2") (pinfunction "2_2") (pintype "passive"))
      (node (ref "STM1") (pin "1") (pinfunction "VBAT_1") (pintype "passive"))
      (node (ref "STM1") (pin "19") (pinfunction "VDD_1_19") (pintype "passive"))
      (node (ref "STM1") (pin "32") (pinfunction "VDD_2_32") (pintype "passive"))
      (node (ref "STM1") (pin "48") (pinfunction "VDD_3_48") (pintype "passive"))
      (node (ref "STM1") (pin "64") (pinfunction "VDD_4_64") (pintype "passive"))
      (node (ref "SWD1") (pin "4") (pinfunction "4_4") (pintype "passive"))
      (node (ref "U3") (pin "2") (pinfunction "3V3_2") (pintype "passive"))
      (node (ref "U4") (pin "3") (pinfunction "VCC_3") (pintype "passive"))
      (node (ref "U6") (pin "3") (pinfunction "VCC_3") (pintype "passive"))
    )
    (net (code "64") (name "VCC-5V") (class "Default")
      (node (ref "C10") (pin "1") (pinfunction "1_1") (pintype "passive"))
      (node (ref "C12") (pin "2") (pinfunction "2_2") (pintype "passive"))
      (node (ref "C13") (pin "2") (pinfunction "2_2") (pintype "passive"))
      (node (ref "DBUS1") (pin "2") (pinfunction "2_2") (pintype "passive"))
      (node (ref "L1") (pin "2") (pinfunction "2_2") (pintype "passive"))
      (node (ref "P1") (pin "1") (pinfunction "1_1") (pintype "passive"))
      (node (ref "P10") (pin "4") (pinfunction "4_4") (pintype "passive"))
      (node (ref "P12") (pin "1") (pinfunction "1_1") (pintype "passive"))
      (node (ref "P5") (pin "2") (pinfunction "2_2") (pintype "passive"))
      (node (ref "P6") (pin "4") (pinfunction "4_4") (pintype "passive"))
      (node (ref "P8") (pin "1") (pinfunction "1_1") (pintype "passive"))
      (node (ref "R10") (pin "1") (pinfunction "TOP_1") (pintype "passive"))
      (node (ref "U3") (pin "3") (pinfunction "5V_3") (pintype "passive"))
    )
    (net (code "65") (name "VCC-24V") (class "Default")
      (node (ref "MOS1") (pin "5") (pinfunction "1_5") (pintype "passive"))
      (node (ref "MOS1") (pin "6") (pinfunction "4_6") (pintype "passive"))
      (node (ref "MOS1") (pin "7") (pinfunction "5_7") (pintype "passive"))
      (node (ref "MOS1") (pin "8") (pinfunction "6_8") (pintype "passive"))
      (node (ref "R1") (pin "1") (pinfunction "1_1") (pintype "passive"))
      (node (ref "U2") (pin "7") (pinfunction "VIN_7") (pintype "power_in"))
    )
    (net (code "66") (name "VCC-A3V3") (class "Default")
      (node (ref "C24") (pin "1") (pinfunction "1_1") (pintype "passive"))
      (node (ref "L3") (pin "2") (pinfunction "2_2") (pintype "passive"))
      (node (ref "STM1") (pin "13") (pinfunction "VDDA_13") (pintype "passive"))
    )
    (net (code "67") (name "VCC-BAT") (class "Default")
      (node (ref "CR1") (pin "2") (pinfunction "12_2") (pintype "passive"))
      (node (ref "MOS1") (pin "1") (pinfunction "3_1") (pintype "passive"))
      (node (ref "MOS1") (pin "2") (pinfunction "7_2") (pintype "passive"))
      (node (ref "MOS1") (pin "3") (pinfunction "8_3") (pintype "passive"))
      (node (ref "P2") (pin "1") (pinfunction "+_1") (pintype "passive"))
      (node (ref "P3") (pin "1") (pinfunction "+_1") (pintype "passive"))
      (node (ref "P4") (pin "1") (pinfunction "+_1") (pintype "passive"))
      (node (ref "R2") (pin "1") (pinfunction "1_1") (pintype "passive"))
      (node (ref "R21") (pin "2") (pinfunction "2_2") (pintype "passive"))
      (node (ref "R3") (pin "1") (pinfunction "1_1") (pintype "passive"))
      (node (ref "R4") (pin "1") (pinfunction "1_1") (pintype "passive"))
      (node (ref "U1") (pin "2") (pinfunction "2_2") (pintype "passive"))
    )
    (net (code "68") (name "unconnected-(M1-Pad0)") (class "Default")
      (node (ref "M1") (pin "0") (pinfunction "0_0") (pintype "passive"))
    )
    (net (code "69") (name "unconnected-(M2-Pad0)") (class "Default")
      (node (ref "M2") (pin "0") (pinfunction "0_0") (pintype "passive"))
    )
    (net (code "70") (name "unconnected-(M3-Pad0)") (class "Default")
      (node (ref "M3") (pin "0") (pinfunction "0_0") (pintype "passive"))
    )
    (net (code "71") (name "unconnected-(M4-Pad0)") (class "Default")
      (node (ref "M4") (pin "0") (pinfunction "0_0") (pintype "passive"))
    )
    (net (code "72") (name "unconnected-(STM1B-PA2-Pad16)") (class "Default")
      (node (ref "STM1") (pin "16") (pinfunction "PA2_16") (pintype "passive"))
    )
    (net (code "73") (name "unconnected-(STM1B-PA8-Pad41)") (class "Default")
      (node (ref "STM1") (pin "41") (pinfunction "PA8_41") (pintype "passive"))
    )
    (net (code "74") (name "unconnected-(STM1B-PA15-Pad50)") (class "Default")
      (node (ref "STM1") (pin "50") (pinfunction "PA15_50") (pintype "passive"))
    )
    (net (code "75") (name "unconnected-(STM1B-PB0-Pad26)") (class "Default")
      (node (ref "STM1") (pin "26") (pinfunction "PB0_26") (pintype "passive"))
    )
    (net (code "76") (name "unconnected-(STM1B-PB3-Pad55)") (class "Default")
      (node (ref "STM1") (pin "55") (pinfunction "PB3_55") (pintype "passive"))
    )
    (net (code "77") (name "unconnected-(STM1B-PB4-Pad56)") (class "Default")
      (node (ref "STM1") (pin "56") (pinfunction "PB4_56") (pintype "passive"))
    )
    (net (code "78") (name "unconnected-(STM1B-PB5-Pad57)") (class "Default")
      (node (ref "STM1") (pin "57") (pinfunction "PB5_57") (pintype "passive"))
    )
    (net (code "79") (name "unconnected-(STM1B-PB6-Pad58)") (class "Default")
      (node (ref "STM1") (pin "58") (pinfunction "PB6_58") (pintype "passive"))
    )
    (net (code "80") (name "unconnected-(STM1B-PB7-Pad59)") (class "Default")
      (node (ref "STM1") (pin "59") (pinfunction "PB7_59") (pintype "passive"))
    )
    (net (code "81") (name "unconnected-(STM1B-PB14-Pad35)") (class "Default")
      (node (ref "STM1") (pin "35") (pinfunction "PB14_35") (pintype "passive"))
    )
    (net (code "82") (name "unconnected-(STM1B-PB15-Pad36)") (class "Default")
      (node (ref "STM1") (pin "36") (pinfunction "PB15_36") (pintype "passive"))
    )
    (net (code "83") (name "unconnected-(STM1B-PC0-Pad8)") (class "Default")
      (node (ref "STM1") (pin "8") (pinfunction "PC0_8") (pintype "passive"))
    )
    (net (code "84") (name "unconnected-(STM1B-PC1-Pad9)") (class "Default")
      (node (ref "STM1") (pin "9") (pinfunction "PC1_9") (pintype "passive"))
    )
    (net (code "85") (name "unconnected-(STM1B-PC2-Pad10)") (class "Default")
      (node (ref "STM1") (pin "10") (pinfunction "PC2_10") (pintype "passive"))
    )
    (net (code "86") (name "unconnected-(STM1B-PC3-Pad11)") (class "Default")
      (node (ref "STM1") (pin "11") (pinfunction "PC3_11") (pintype "passive"))
    )
    (net (code "87") (name "unconnected-(STM1B-PC5-Pad25)") (class "Default")
      (node (ref "STM1") (pin "25") (pinfunction "PC5_25") (pintype "passive"))
    )
    (net (code "88") (name "unconnected-(STM1B-PC10-Pad51)") (class "Default")
      (node (ref "STM1") (pin "51") (pinfunction "PC10_51") (pintype "passive"))
    )
    (net (code "89") (name "unconnected-(STM1B-PC13-Pad2)") (class "Default")
      (node (ref "STM1") (pin "2") (pinfunction "PC13_2") (pintype "passive"))
    )
    (net (code "90") (name "unconnected-(STM1B-PC14-Pad3)") (class "Default")
      (node (ref "STM1") (pin "3") (pinfunction "PC14_3") (pintype "passive"))
    )
    (net (code "91") (name "unconnected-(STM1B-PC15-Pad4)") (class "Default")
      (node (ref "STM1") (pin "4") (pinfunction "PC15_4") (pintype "passive"))
    )
    (net (code "92") (name "unconnected-(U2-ENA-Pad5)") (class "Default")
      (node (ref "U2") (pin "5") (pinfunction "ENA_5") (pintype "power_in+no_connect"))
    )
    (net (code "93") (name "unconnected-(U2-NC-Pad2)") (class "Default")
      (node (ref "U2") (pin "2") (pinfunction "NC_2") (pintype "power_in+no_connect"))
    )
    (net (code "94") (name "unconnected-(U2-NC-Pad3)") (class "Default")
      (node (ref "U2") (pin "3") (pinfunction "NC_3") (pintype "power_in+no_connect"))
    )
    (net (code "95") (name "unconnected-(U4-RS-Pad8)") (class "Default")
      (node (ref "U4") (pin "8") (pinfunction "RS_8") (pintype "passive"))
    )
    (net (code "96") (name "unconnected-(U4-VREF-Pad5)") (class "Default")
      (node (ref "U4") (pin "5") (pinfunction "VREF_5") (pintype "passive"))
    )
    (net (code "97") (name "unconnected-(U5-IO7-Pad7)") (class "Default")
      (node (ref "U5") (pin "7") (pinfunction "IO7_7") (pintype "passive"))
    )
    (net (code "98") (name "unconnected-(U5-IO10-Pad10)") (class "Default")
      (node (ref "U5") (pin "10") (pinfunction "IO10_10") (pintype "passive"))
    )
    (net (code "99") (name "unconnected-(U5-IO11-Pad11)") (class "Default")
      (node (ref "U5") (pin "11") (pinfunction "IO11_11") (pintype "passive"))
    )
    (net (code "100") (name "unconnected-(U5-IO21-Pad21)") (class "Default")
      (node (ref "U5") (pin "21") (pinfunction "IO21_21") (pintype "passive"))
    )
    (net (code "101") (name "unconnected-(U5-IO22-Pad22)") (class "Default")
      (node (ref "U5") (pin "22") (pinfunction "IO22_22") (pintype "passive"))
    )
    (net (code "102") (name "unconnected-(U5-IO23-Pad23)") (class "Default")
      (node (ref "U5") (pin "23") (pinfunction "IO23_23") (pintype "passive"))
    )
    (net (code "103") (name "unconnected-(U5-IO25-Pad25)") (class "Default")
      (node (ref "U5") (pin "25") (pinfunction "IO25_25") (pintype "passive"))
    )
    (net (code "104") (name "unconnected-(U6-RS-Pad8)") (class "Default")
      (node (ref "U6") (pin "8") (pinfunction "RS_8") (pintype "passive"))
    )
    (net (code "105") (name "unconnected-(U6-VREF-Pad5)") (class "Default")
      (node (ref "U6") (pin "5") (pinfunction "VREF_5") (pintype "passive"))
    )
  )
)
